# RelayModule_RELAY.net
KiCad netlist of a schematic drawn in Altium Designer
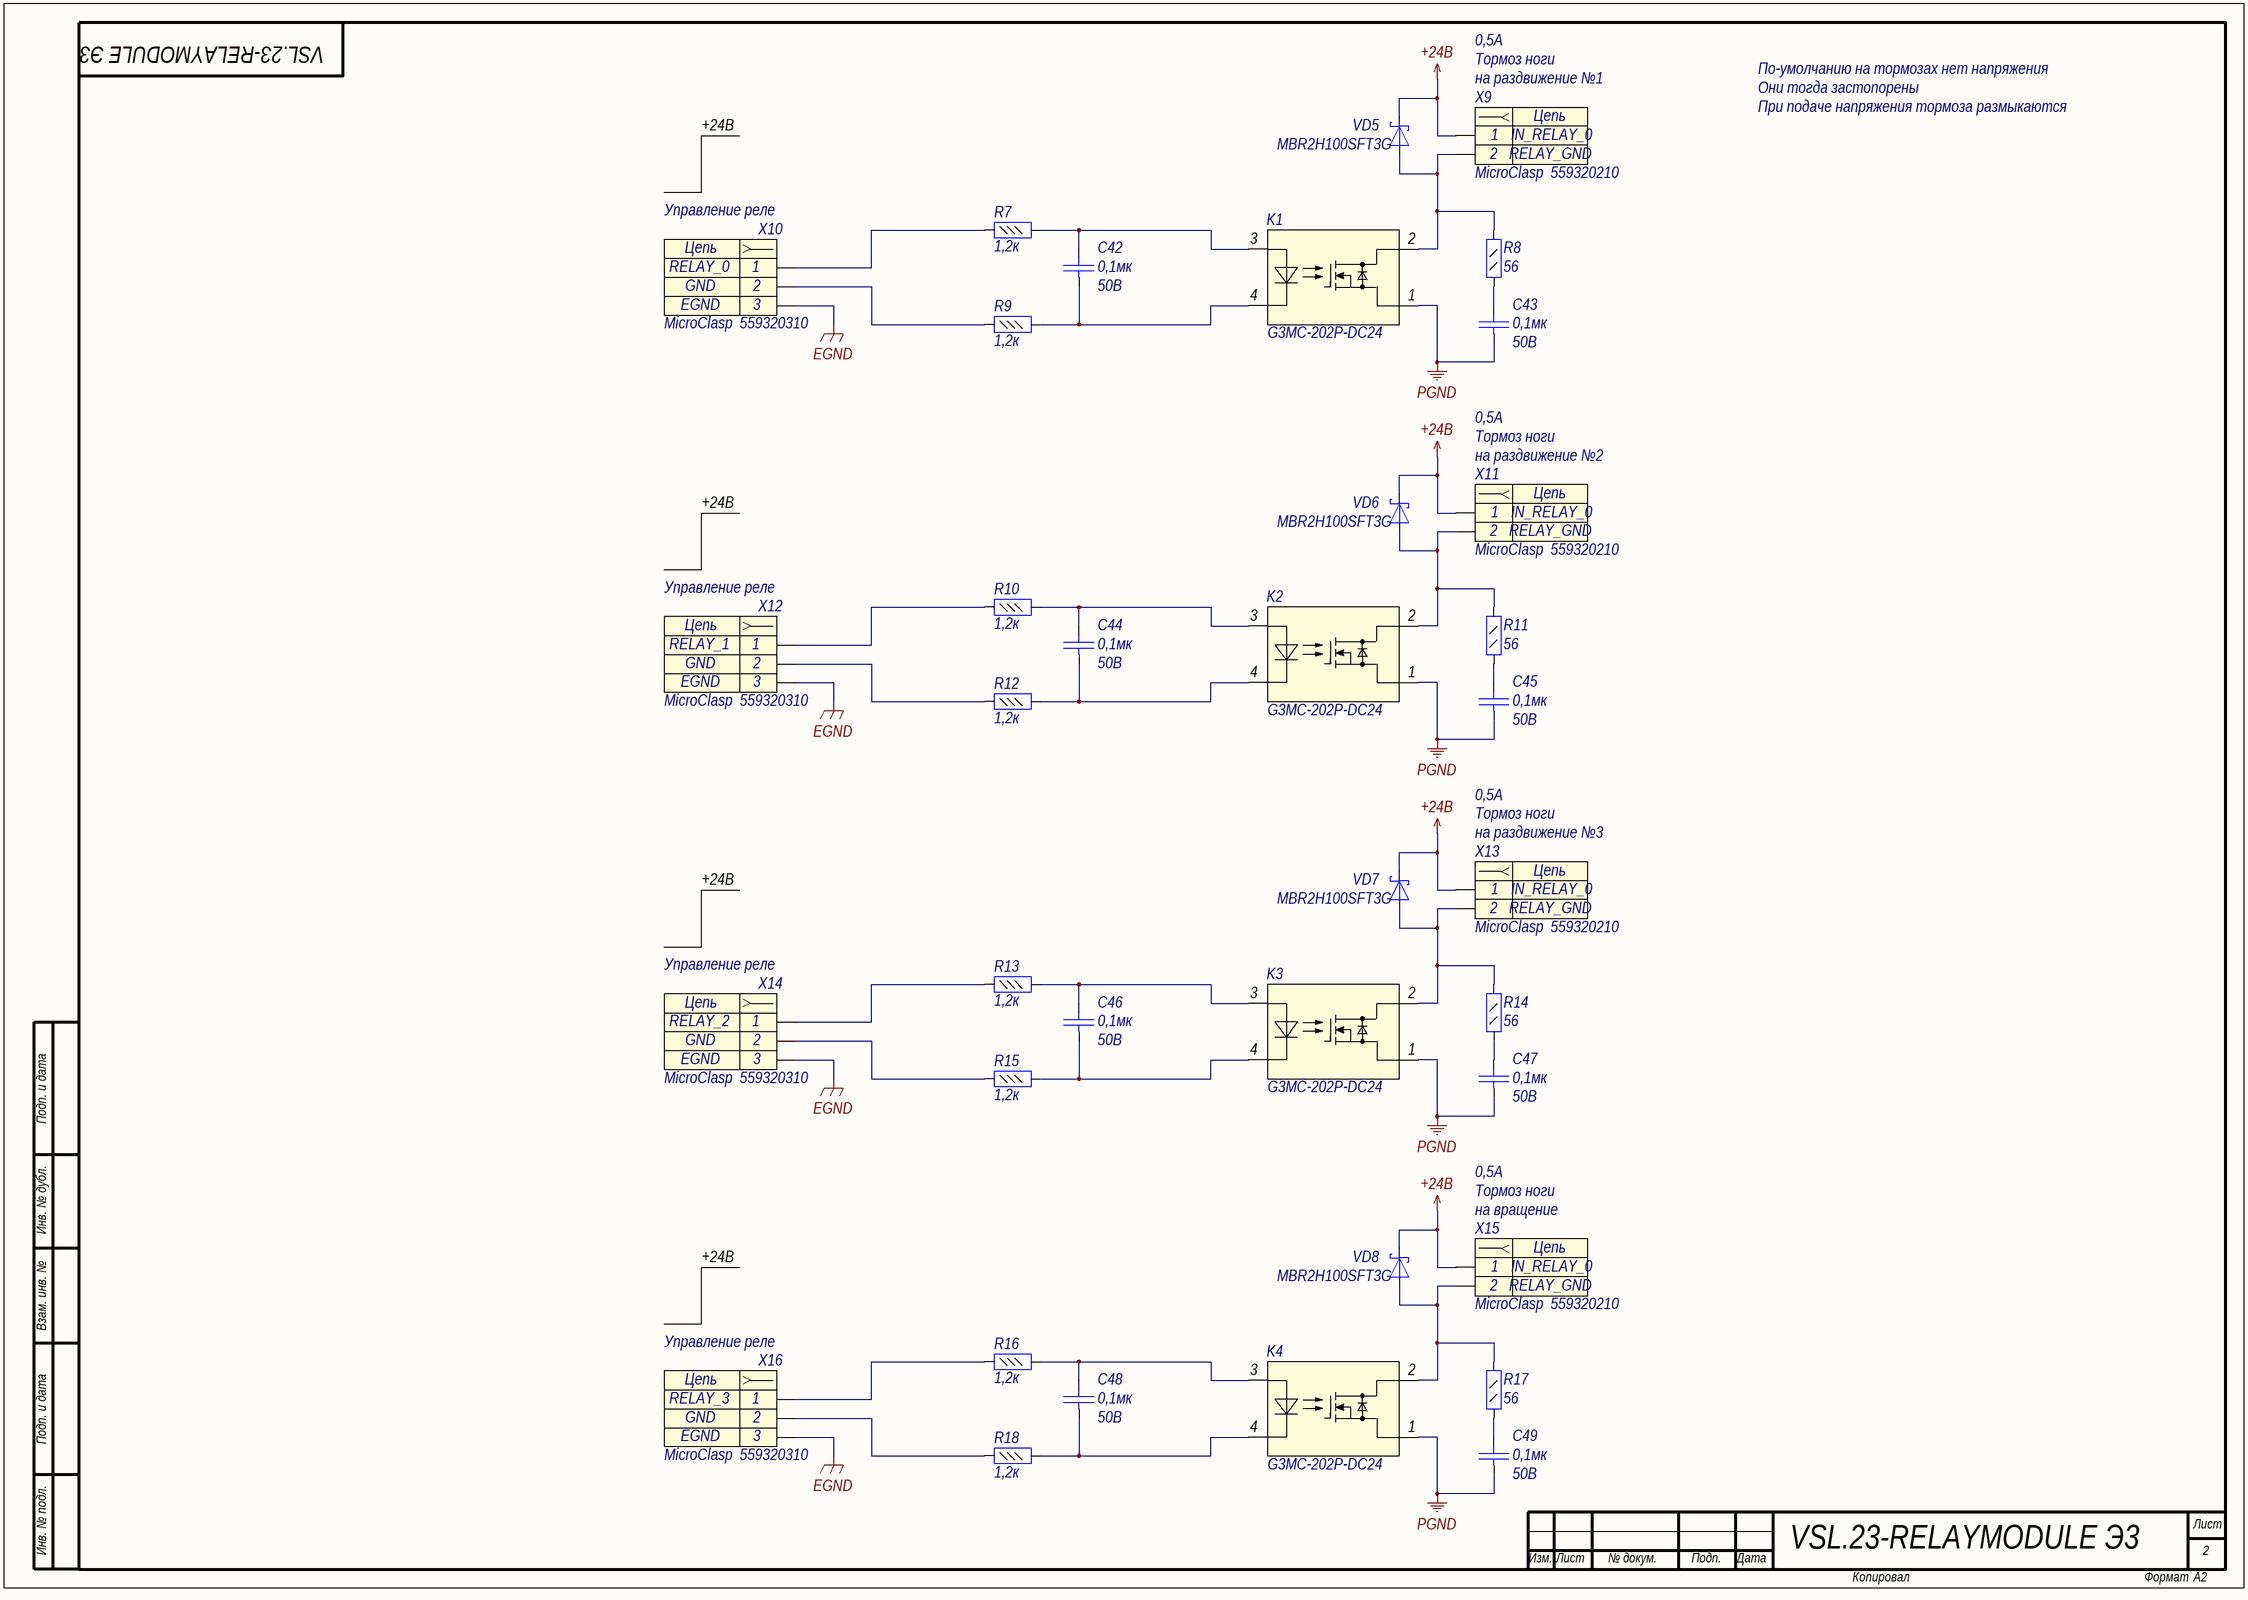
[diagram p0: RelayModule_RELAY.SchDoc]

(export (version "E")
  (design (tool "Eeschema 10.0.6"))
  (components
    (comp (ref "C42")
      (value "0,1мк")
      (footprint "C0402")
      (description "Конденсатор")
      (fields (field (name "VOLTAGE") "50В") (field (name "PART NUMBER") "GRM155R71H104KE14D "))
      (libsource (lib "MOP44") (part "Capacitor"))
    )
    (comp (ref "C43")
      (value "0,1мк")
      (footprint "C0402")
      (description "Конденсатор")
      (fields (field (name "VOLTAGE") "50В") (field (name "PART NUMBER") "GRM155R71H104KE14D "))
      (libsource (lib "MOP44") (part "Capacitor"))
    )
    (comp (ref "C44")
      (value "0,1мк")
      (footprint "C0402")
      (description "Конденсатор")
      (fields (field (name "VOLTAGE") "50В") (field (name "PART NUMBER") "GRM155R71H104KE14D "))
      (libsource (lib "MOP44") (part "Capacitor"))
    )
    (comp (ref "C45")
      (value "0,1мк")
      (footprint "C0402")
      (description "Конденсатор")
      (fields (field (name "VOLTAGE") "50В") (field (name "PART NUMBER") "GRM155R71H104KE14D "))
      (libsource (lib "MOP44") (part "Capacitor"))
    )
    (comp (ref "C46")
      (value "0,1мк")
      (footprint "C0402")
      (description "Конденсатор")
      (fields (field (name "VOLTAGE") "50В") (field (name "PART NUMBER") "GRM155R71H104KE14D "))
      (libsource (lib "MOP44") (part "Capacitor"))
    )
    (comp (ref "C47")
      (value "0,1мк")
      (footprint "C0402")
      (description "Конденсатор")
      (fields (field (name "VOLTAGE") "50В") (field (name "PART NUMBER") "GRM155R71H104KE14D "))
      (libsource (lib "MOP44") (part "Capacitor"))
    )
    (comp (ref "C48")
      (value "0,1мк")
      (footprint "C0402")
      (description "Конденсатор")
      (fields (field (name "VOLTAGE") "50В") (field (name "PART NUMBER") "GRM155R71H104KE14D "))
      (libsource (lib "MOP44") (part "Capacitor"))
    )
    (comp (ref "C49")
      (value "0,1мк")
      (footprint "C0402")
      (description "Конденсатор")
      (fields (field (name "VOLTAGE") "50В") (field (name "PART NUMBER") "GRM155R71H104KE14D "))
      (libsource (lib "MOP44") (part "Capacitor"))
    )
    (comp (ref "K1")
      (value "Relay_SSR")
      (footprint "SIP4")
      (description "Твердотельное реле")
      (fields (field (name "PART NUMBER") "G3MC-202P-DC24"))
      (libsource (lib "MOP44") (part "Relay_SSR"))
    )
    (comp (ref "K2")
      (value "Relay_SSR")
      (footprint "SIP4")
      (description "Твердотельное реле")
      (fields (field (name "PART NUMBER") "G3MC-202P-DC24"))
      (libsource (lib "MOP44") (part "Relay_SSR"))
    )
    (comp (ref "K3")
      (value "Relay_SSR")
      (footprint "SIP4")
      (description "Твердотельное реле")
      (fields (field (name "PART NUMBER") "G3MC-202P-DC24"))
      (libsource (lib "MOP44") (part "Relay_SSR"))
    )
    (comp (ref "K4")
      (value "Relay_SSR")
      (footprint "SIP4")
      (description "Твердотельное реле")
      (fields (field (name "PART NUMBER") "G3MC-202P-DC24"))
      (libsource (lib "MOP44") (part "Relay_SSR"))
    )
    (comp (ref "R7")
      (value "1,2к")
      (footprint "R0402")
      (description "Резистор")
      (fields (field (name "PART NUMBER") "RC0402FR-071K2") (field (name "POWER") "0,062Вт"))
      (libsource (lib "MOP44") (part "Resistor_0,062Вт"))
    )
    (comp (ref "R8")
      (value "56")
      (footprint "R0805")
      (description "Резистор")
      (fields (field (name "PART NUMBER") "RC0805FR-0756RL") (field (name "POWER") "0,125Вт"))
      (libsource (lib "MOP44") (part "Resistor_0,125Вт"))
    )
    (comp (ref "R9")
      (value "1,2к")
      (footprint "R0402")
      (description "Резистор")
      (fields (field (name "PART NUMBER") "RC0402FR-071K2") (field (name "POWER") "0,062Вт"))
      (libsource (lib "MOP44") (part "Resistor_0,062Вт"))
    )
    (comp (ref "R10")
      (value "1,2к")
      (footprint "R0402")
      (description "Резистор")
      (fields (field (name "PART NUMBER") "RC0402FR-071K2") (field (name "POWER") "0,062Вт"))
      (libsource (lib "MOP44") (part "Resistor_0,062Вт"))
    )
    (comp (ref "R11")
      (value "56")
      (footprint "R0805")
      (description "Резистор")
      (fields (field (name "PART NUMBER") "RC0805FR-0756RL") (field (name "POWER") "0,125Вт"))
      (libsource (lib "MOP44") (part "Resistor_0,125Вт"))
    )
    (comp (ref "R12")
      (value "1,2к")
      (footprint "R0402")
      (description "Резистор")
      (fields (field (name "PART NUMBER") "RC0402FR-071K2") (field (name "POWER") "0,062Вт"))
      (libsource (lib "MOP44") (part "Resistor_0,062Вт"))
    )
    (comp (ref "R13")
      (value "1,2к")
      (footprint "R0402")
      (description "Резистор")
      (fields (field (name "PART NUMBER") "RC0402FR-071K2") (field (name "POWER") "0,062Вт"))
      (libsource (lib "MOP44") (part "Resistor_0,062Вт"))
    )
    (comp (ref "R14")
      (value "56")
      (footprint "R0805")
      (description "Резистор")
      (fields (field (name "PART NUMBER") "RC0805FR-0756RL") (field (name "POWER") "0,125Вт"))
      (libsource (lib "MOP44") (part "Resistor_0,125Вт"))
    )
    (comp (ref "R15")
      (value "1,2к")
      (footprint "R0402")
      (description "Резистор")
      (fields (field (name "PART NUMBER") "RC0402FR-071K2") (field (name "POWER") "0,062Вт"))
      (libsource (lib "MOP44") (part "Resistor_0,062Вт"))
    )
    (comp (ref "R16")
      (value "1,2к")
      (footprint "R0402")
      (description "Резистор")
      (fields (field (name "PART NUMBER") "RC0402FR-071K2") (field (name "POWER") "0,062Вт"))
      (libsource (lib "MOP44") (part "Resistor_0,062Вт"))
    )
    (comp (ref "R17")
      (value "56")
      (footprint "R0805")
      (description "Резистор")
      (fields (field (name "PART NUMBER") "RC0805FR-0756RL") (field (name "POWER") "0,125Вт"))
      (libsource (lib "MOP44") (part "Resistor_0,125Вт"))
    )
    (comp (ref "R18")
      (value "1,2к")
      (footprint "R0402")
      (description "Резистор")
      (fields (field (name "PART NUMBER") "RC0402FR-071K2") (field (name "POWER") "0,062Вт"))
      (libsource (lib "MOP44") (part "Resistor_0,062Вт"))
    )
    (comp (ref "VD5")
      (value "DiodeSchottky")
      (footprint "SOD-123")
      (description "Диод Шоттки")
      (fields (field (name "PART NUMBER") "MBR2H100SFT3G"))
      (libsource (lib "MOP44") (part "DiodeSchottky"))
    )
    (comp (ref "VD6")
      (value "DiodeSchottky")
      (footprint "SOD-123")
      (description "Диод Шоттки")
      (fields (field (name "PART NUMBER") "MBR2H100SFT3G"))
      (libsource (lib "MOP44") (part "DiodeSchottky"))
    )
    (comp (ref "VD7")
      (value "DiodeSchottky")
      (footprint "SOD-123")
      (description "Диод Шоттки")
      (fields (field (name "PART NUMBER") "MBR2H100SFT3G"))
      (libsource (lib "MOP44") (part "DiodeSchottky"))
    )
    (comp (ref "VD8")
      (value "DiodeSchottky")
      (footprint "SOD-123")
      (description "Диод Шоттки")
      (fields (field (name "PART NUMBER") "MBR2H100SFT3G"))
      (libsource (lib "MOP44") (part "DiodeSchottky"))
    )
    (comp (ref "X9")
      (value "Header_2_sct")
      (footprint "MOLEX_559320210")
      (description "Разъем - 2 конт. розетка")
      (fields (field (name "PART NAME") "MicroClasp") (field (name "PART NUMBER") "559320210"))
      (libsource (lib "MOP44") (part "Header_2_sct"))
    )
    (comp (ref "X10")
      (value "Управление реле")
      (footprint "MOLEX_559320310")
      (description "Разъем - 3 конт. розетка")
      (fields (field (name "PART NAME") "MicroClasp") (field (name "PART NUMBER") "559320310"))
      (libsource (lib "MOP44") (part "Header_3_sct"))
    )
    (comp (ref "X11")
      (value "Header_2_sct")
      (footprint "MOLEX_559320210")
      (description "Разъем - 2 конт. розетка")
      (fields (field (name "PART NAME") "MicroClasp") (field (name "PART NUMBER") "559320210"))
      (libsource (lib "MOP44") (part "Header_2_sct"))
    )
    (comp (ref "X12")
      (value "Управление реле")
      (footprint "MOLEX_559320310")
      (description "Разъем - 3 конт. розетка")
      (fields (field (name "PART NAME") "MicroClasp") (field (name "PART NUMBER") "559320310"))
      (libsource (lib "MOP44") (part "Header_3_sct"))
    )
    (comp (ref "X13")
      (value "Header_2_sct")
      (footprint "MOLEX_559320210")
      (description "Разъем - 2 конт. розетка")
      (fields (field (name "PART NAME") "MicroClasp") (field (name "PART NUMBER") "559320210"))
      (libsource (lib "MOP44") (part "Header_2_sct"))
    )
    (comp (ref "X14")
      (value "Управление реле")
      (footprint "MOLEX_559320310")
      (description "Разъем - 3 конт. розетка")
      (fields (field (name "PART NAME") "MicroClasp") (field (name "PART NUMBER") "559320310"))
      (libsource (lib "MOP44") (part "Header_3_sct"))
    )
    (comp (ref "X15")
      (value "Header_2_sct")
      (footprint "MOLEX_559320210")
      (description "Разъем - 2 конт. розетка")
      (fields (field (name "PART NAME") "MicroClasp") (field (name "PART NUMBER") "559320210"))
      (libsource (lib "MOP44") (part "Header_2_sct"))
    )
    (comp (ref "X16")
      (value "Управление реле")
      (footprint "MOLEX_559320310")
      (description "Разъем - 3 конт. розетка")
      (fields (field (name "PART NAME") "MicroClasp") (field (name "PART NUMBER") "559320310"))
      (libsource (lib "MOP44") (part "Header_3_sct"))
    )
  )
  (nets
    (net (code "1") (name "+24B") (class "Default")
      (node (ref "VD5") (pin "1") (pinfunction "K_1") (pintype "passive"))
      (node (ref "VD6") (pin "1") (pinfunction "K_1") (pintype "passive"))
      (node (ref "VD7") (pin "1") (pinfunction "K_1") (pintype "passive"))
      (node (ref "VD8") (pin "1") (pinfunction "K_1") (pintype "passive"))
      (node (ref "X11") (pin "1") (pinfunction "1_1") (pintype "passive"))
      (node (ref "X13") (pin "1") (pinfunction "1_1") (pintype "passive"))
      (node (ref "X15") (pin "1") (pinfunction "1_1") (pintype "passive"))
      (node (ref "X9") (pin "1") (pinfunction "1_1") (pintype "passive"))
    )
    (net (code "2") (name "EGND") (class "Default")
      (node (ref "X10") (pin "3") (pinfunction "3_3") (pintype "passive"))
      (node (ref "X12") (pin "3") (pinfunction "3_3") (pintype "passive"))
      (node (ref "X14") (pin "3") (pinfunction "3_3") (pintype "passive"))
      (node (ref "X16") (pin "3") (pinfunction "3_3") (pintype "passive"))
    )
    (net (code "3") (name "Net-(C42-Pad1)") (class "Default")
      (node (ref "C42") (pin "1") (pinfunction "1_1") (pintype "passive"))
      (node (ref "K1") (pin "4") (pintype "passive"))
      (node (ref "R9") (pin "2") (pinfunction "2_2") (pintype "passive"))
    )
    (net (code "4") (name "Net-(C43-Pad2)") (class "Default")
      (node (ref "C43") (pin "2") (pinfunction "2_2") (pintype "passive"))
      (node (ref "R8") (pin "1") (pinfunction "1_1") (pintype "passive"))
    )
    (net (code "5") (name "Net-(C44-Pad1)") (class "Default")
      (node (ref "C44") (pin "1") (pinfunction "1_1") (pintype "passive"))
      (node (ref "K2") (pin "4") (pintype "passive"))
      (node (ref "R12") (pin "2") (pinfunction "2_2") (pintype "passive"))
    )
    (net (code "6") (name "Net-(C45-Pad2)") (class "Default")
      (node (ref "C45") (pin "2") (pinfunction "2_2") (pintype "passive"))
      (node (ref "R11") (pin "1") (pinfunction "1_1") (pintype "passive"))
    )
    (net (code "7") (name "Net-(C46-Pad1)") (class "Default")
      (node (ref "C46") (pin "1") (pinfunction "1_1") (pintype "passive"))
      (node (ref "K3") (pin "4") (pintype "passive"))
      (node (ref "R15") (pin "2") (pinfunction "2_2") (pintype "passive"))
    )
    (net (code "8") (name "Net-(C47-Pad2)") (class "Default")
      (node (ref "C47") (pin "2") (pinfunction "2_2") (pintype "passive"))
      (node (ref "R14") (pin "1") (pinfunction "1_1") (pintype "passive"))
    )
    (net (code "9") (name "Net-(C48-Pad1)") (class "Default")
      (node (ref "C48") (pin "1") (pinfunction "1_1") (pintype "passive"))
      (node (ref "K4") (pin "4") (pintype "passive"))
      (node (ref "R18") (pin "2") (pinfunction "2_2") (pintype "passive"))
    )
    (net (code "10") (name "Net-(C49-Pad2)") (class "Default")
      (node (ref "C49") (pin "2") (pinfunction "2_2") (pintype "passive"))
      (node (ref "R17") (pin "1") (pinfunction "1_1") (pintype "passive"))
    )
    (net (code "11") (name "Net-(K1-+)") (class "Default")
      (node (ref "C42") (pin "2") (pinfunction "2_2") (pintype "passive"))
      (node (ref "K1") (pin "3") (pinfunction "+_3") (pintype "passive"))
      (node (ref "R7") (pin "2") (pinfunction "2_2") (pintype "passive"))
    )
    (net (code "12") (name "Net-(K2-+)") (class "Default")
      (node (ref "C44") (pin "2") (pinfunction "2_2") (pintype "passive"))
      (node (ref "K2") (pin "3") (pinfunction "+_3") (pintype "passive"))
      (node (ref "R10") (pin "2") (pinfunction "2_2") (pintype "passive"))
    )
    (net (code "13") (name "Net-(K3-+)") (class "Default")
      (node (ref "C46") (pin "2") (pinfunction "2_2") (pintype "passive"))
      (node (ref "K3") (pin "3") (pinfunction "+_3") (pintype "passive"))
      (node (ref "R13") (pin "2") (pinfunction "2_2") (pintype "passive"))
    )
    (net (code "14") (name "Net-(K4-+)") (class "Default")
      (node (ref "C48") (pin "2") (pinfunction "2_2") (pintype "passive"))
      (node (ref "K4") (pin "3") (pinfunction "+_3") (pintype "passive"))
      (node (ref "R16") (pin "2") (pinfunction "2_2") (pintype "passive"))
    )
    (net (code "15") (name "Net-(R7-Pad1)") (class "Default")
      (node (ref "R7") (pin "1") (pinfunction "1_1") (pintype "passive"))
      (node (ref "X10") (pin "1") (pinfunction "1_1") (pintype "passive"))
    )
    (net (code "16") (name "Net-(R9-Pad1)") (class "Default")
      (node (ref "R9") (pin "1") (pinfunction "1_1") (pintype "passive"))
      (node (ref "X10") (pin "2") (pinfunction "2_2") (pintype "passive"))
    )
    (net (code "17") (name "Net-(R10-Pad1)") (class "Default")
      (node (ref "R10") (pin "1") (pinfunction "1_1") (pintype "passive"))
      (node (ref "X12") (pin "1") (pinfunction "1_1") (pintype "passive"))
    )
    (net (code "18") (name "Net-(R12-Pad1)") (class "Default")
      (node (ref "R12") (pin "1") (pinfunction "1_1") (pintype "passive"))
      (node (ref "X12") (pin "2") (pinfunction "2_2") (pintype "passive"))
    )
    (net (code "19") (name "Net-(R13-Pad1)") (class "Default")
      (node (ref "R13") (pin "1") (pinfunction "1_1") (pintype "passive"))
      (node (ref "X14") (pin "1") (pinfunction "1_1") (pintype "passive"))
    )
    (net (code "20") (name "Net-(R15-Pad1)") (class "Default")
      (node (ref "R15") (pin "1") (pinfunction "1_1") (pintype "passive"))
      (node (ref "X14") (pin "2") (pinfunction "2_2") (pintype "passive"))
    )
    (net (code "21") (name "Net-(R16-Pad1)") (class "Default")
      (node (ref "R16") (pin "1") (pinfunction "1_1") (pintype "passive"))
      (node (ref "X16") (pin "1") (pinfunction "1_1") (pintype "passive"))
    )
    (net (code "22") (name "Net-(R18-Pad1)") (class "Default")
      (node (ref "R18") (pin "1") (pinfunction "1_1") (pintype "passive"))
      (node (ref "X16") (pin "2") (pinfunction "2_2") (pintype "passive"))
    )
    (net (code "23") (name "Net-(VD5-A)") (class "Default")
      (node (ref "K1") (pin "2") (pintype "passive"))
      (node (ref "R8") (pin "2") (pinfunction "2_2") (pintype "passive"))
      (node (ref "VD5") (pin "2") (pinfunction "A_2") (pintype "passive"))
      (node (ref "X9") (pin "2") (pinfunction "2_2") (pintype "passive"))
    )
    (net (code "24") (name "Net-(VD6-A)") (class "Default")
      (node (ref "K2") (pin "2") (pintype "passive"))
      (node (ref "R11") (pin "2") (pinfunction "2_2") (pintype "passive"))
      (node (ref "VD6") (pin "2") (pinfunction "A_2") (pintype "passive"))
      (node (ref "X11") (pin "2") (pinfunction "2_2") (pintype "passive"))
    )
    (net (code "25") (name "Net-(VD7-A)") (class "Default")
      (node (ref "K3") (pin "2") (pintype "passive"))
      (node (ref "R14") (pin "2") (pinfunction "2_2") (pintype "passive"))
      (node (ref "VD7") (pin "2") (pinfunction "A_2") (pintype "passive"))
      (node (ref "X13") (pin "2") (pinfunction "2_2") (pintype "passive"))
    )
    (net (code "26") (name "Net-(VD8-A)") (class "Default")
      (node (ref "K4") (pin "2") (pintype "passive"))
      (node (ref "R17") (pin "2") (pinfunction "2_2") (pintype "passive"))
      (node (ref "VD8") (pin "2") (pinfunction "A_2") (pintype "passive"))
      (node (ref "X15") (pin "2") (pinfunction "2_2") (pintype "passive"))
    )
    (net (code "27") (name "PGND") (class "Default")
      (node (ref "C43") (pin "1") (pinfunction "1_1") (pintype "passive"))
      (node (ref "C45") (pin "1") (pinfunction "1_1") (pintype "passive"))
      (node (ref "C47") (pin "1") (pinfunction "1_1") (pintype "passive"))
      (node (ref "C49") (pin "1") (pinfunction "1_1") (pintype "passive"))
      (node (ref "K1") (pin "1") (pintype "passive"))
      (node (ref "K2") (pin "1") (pintype "passive"))
      (node (ref "K3") (pin "1") (pintype "passive"))
      (node (ref "K4") (pin "1") (pintype "passive"))
    )
  )
)
